# mic.net
KiCad netlist of a schematic drawn in Altium Designer
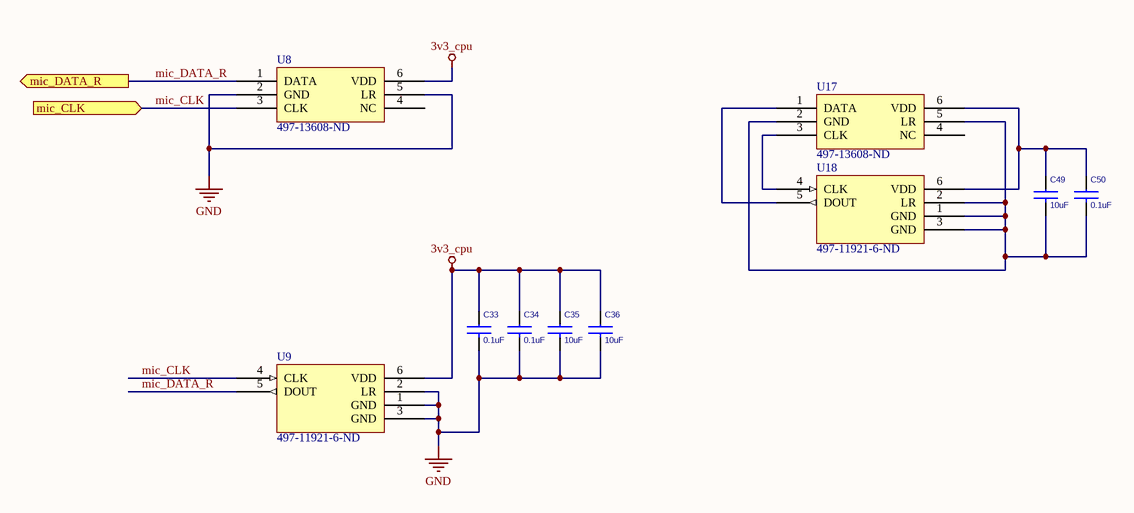
[diagram p0: mic.SchDoc]

(export (version "E")
  (design (tool "Eeschema 10.0.6"))
  (components
    (comp (ref "C33")
      (value "0.1uF")
      (footprint "CAPC2012X09M")
      (description "CAP CER 0.1UF 25V 10% X7R 0805")
      (libsource (lib "Capacitors") (part "CAP_SMD_0.1UF_10%"))
    )
    (comp (ref "C34")
      (value "0.1uF")
      (footprint "CAPC2012X09M")
      (description "CAP CER 0.1UF 25V 10% X7R 0805")
      (libsource (lib "Capacitors") (part "CAP_SMD_0.1UF_10%"))
    )
    (comp (ref "C35")
      (value "10uF")
      (footprint "CAPC2012X09M")
      (description "CAP CER 10UF 16V 20% X5R 0805")
      (libsource (lib "Capacitors") (part "CAP_SMD_10UF_20%"))
    )
    (comp (ref "C36")
      (value "10uF")
      (footprint "CAPC2012X09M")
      (description "CAP CER 10UF 16V 20% X5R 0805")
      (libsource (lib "Capacitors") (part "CAP_SMD_10UF_20%"))
    )
    (comp (ref "C49")
      (value "10uF")
      (footprint "CAPC2012X09M")
      (description "CAP CER 10UF 16V 20% X5R 0805")
      (libsource (lib "Capacitors") (part "CAP_SMD_10UF_20%"))
    )
    (comp (ref "C50")
      (value "0.1uF")
      (footprint "CAPC2012X09M")
      (description "CAP CER 0.1UF 25V 10% X7R 0805")
      (libsource (lib "Capacitors") (part "CAP_SMD_0.1UF_10%"))
    )
    (comp (ref "U8")
      (value "STEVAL-MKI129V1")
      (footprint "STEVAL-MKI129V1")
      (fields (field (name "SUPPLIER PART NUMBER 1") "497-13608-ND"))
      (libsource (lib "TruthEar") (part "STEVAL-MKI129V1"))
    )
    (comp (ref "U9")
      (value "MP45DT02")
      (footprint "LGA6C165P2X3_376X472X125")
      (fields (field (name "SUPPLIER PART NUMBER 1") "497-11921-6-ND"))
      (libsource (lib "TruthEar") (part "MP45DT02"))
    )
    (comp (ref "U17")
      (value "STEVAL-MKI129V1")
      (footprint "STEVAL-MKI129V1")
      (fields (field (name "SUPPLIER PART NUMBER 1") "497-13608-ND"))
      (libsource (lib "TruthEar") (part "STEVAL-MKI129V1"))
    )
    (comp (ref "U18")
      (value "MP45DT02")
      (footprint "LGA6C165P2X3_376X472X125")
      (fields (field (name "SUPPLIER PART NUMBER 1") "497-11921-6-ND"))
      (libsource (lib "TruthEar") (part "MP45DT02"))
    )
  )
  (nets
    (net (code "1") (name "/mic_CLK") (class "Default")
      (node (ref "U8") (pin "3") (pinfunction "CLK_3") (pintype "power_in"))
      (node (ref "U9") (pin "4") (pinfunction "CLK_4") (pintype "input"))
    )
    (net (code "2") (name "/mic_DATA_R") (class "Default")
      (node (ref "U8") (pin "1") (pinfunction "DATA_1") (pintype "power_in"))
      (node (ref "U9") (pin "5") (pinfunction "DOUT_5") (pintype "output"))
    )
    (net (code "3") (name "3v3_cpu") (class "Default")
      (node (ref "C33") (pin "1") (pinfunction "1_1") (pintype "passive"))
      (node (ref "C34") (pin "1") (pinfunction "1_1") (pintype "passive"))
      (node (ref "C35") (pin "1") (pinfunction "1_1") (pintype "passive"))
      (node (ref "C36") (pin "1") (pinfunction "1_1") (pintype "passive"))
      (node (ref "U8") (pin "6") (pinfunction "VDD_6") (pintype "power_in"))
      (node (ref "U9") (pin "6") (pinfunction "VDD_6") (pintype "power_in"))
    )
    (net (code "4") (name "GND") (class "Default")
      (node (ref "C33") (pin "2") (pinfunction "2_2") (pintype "passive"))
      (node (ref "C34") (pin "2") (pinfunction "2_2") (pintype "passive"))
      (node (ref "C35") (pin "2") (pinfunction "2_2") (pintype "passive"))
      (node (ref "C36") (pin "2") (pinfunction "2_2") (pintype "passive"))
      (node (ref "U8") (pin "2") (pinfunction "GND_2") (pintype "power_in"))
      (node (ref "U8") (pin "5") (pinfunction "LR_5") (pintype "power_in"))
      (node (ref "U9") (pin "1") (pinfunction "GND_1") (pintype "power_in"))
      (node (ref "U9") (pin "2") (pinfunction "LR_2") (pintype "power_in"))
      (node (ref "U9") (pin "3") (pinfunction "GND_3") (pintype "power_in"))
    )
    (net (code "5") (name "Net-(U17-CLK)") (class "Default")
      (node (ref "U17") (pin "3") (pinfunction "CLK_3") (pintype "power_in"))
      (node (ref "U18") (pin "4") (pinfunction "CLK_4") (pintype "input"))
    )
    (net (code "6") (name "Net-(U17-DATA)") (class "Default")
      (node (ref "U17") (pin "1") (pinfunction "DATA_1") (pintype "power_in"))
      (node (ref "U18") (pin "5") (pinfunction "DOUT_5") (pintype "output"))
    )
    (net (code "7") (name "Net-(U17-GND)") (class "Default")
      (node (ref "C49") (pin "2") (pinfunction "2_2") (pintype "passive"))
      (node (ref "C50") (pin "2") (pinfunction "2_2") (pintype "passive"))
      (node (ref "U17") (pin "2") (pinfunction "GND_2") (pintype "power_in"))
      (node (ref "U17") (pin "5") (pinfunction "LR_5") (pintype "power_in"))
      (node (ref "U18") (pin "1") (pinfunction "GND_1") (pintype "power_in"))
      (node (ref "U18") (pin "2") (pinfunction "LR_2") (pintype "power_in"))
      (node (ref "U18") (pin "3") (pinfunction "GND_3") (pintype "power_in"))
    )
    (net (code "8") (name "Net-(U17-VDD)") (class "Default")
      (node (ref "C49") (pin "1") (pinfunction "1_1") (pintype "passive"))
      (node (ref "C50") (pin "1") (pinfunction "1_1") (pintype "passive"))
      (node (ref "U17") (pin "6") (pinfunction "VDD_6") (pintype "power_in"))
      (node (ref "U18") (pin "6") (pinfunction "VDD_6") (pintype "power_in"))
    )
    (net (code "9") (name "unconnected-(U8-NC-Pad4)") (class "Default")
      (node (ref "U8") (pin "4") (pinfunction "NC_4") (pintype "power_in"))
    )
    (net (code "10") (name "unconnected-(U17-NC-Pad4)") (class "Default")
      (node (ref "U17") (pin "4") (pinfunction "NC_4") (pintype "power_in"))
    )
  )
)
